# SCH_gauges_v2_2023-05-08.net
KiCad netlist of a schematic drawn in EasyEDA
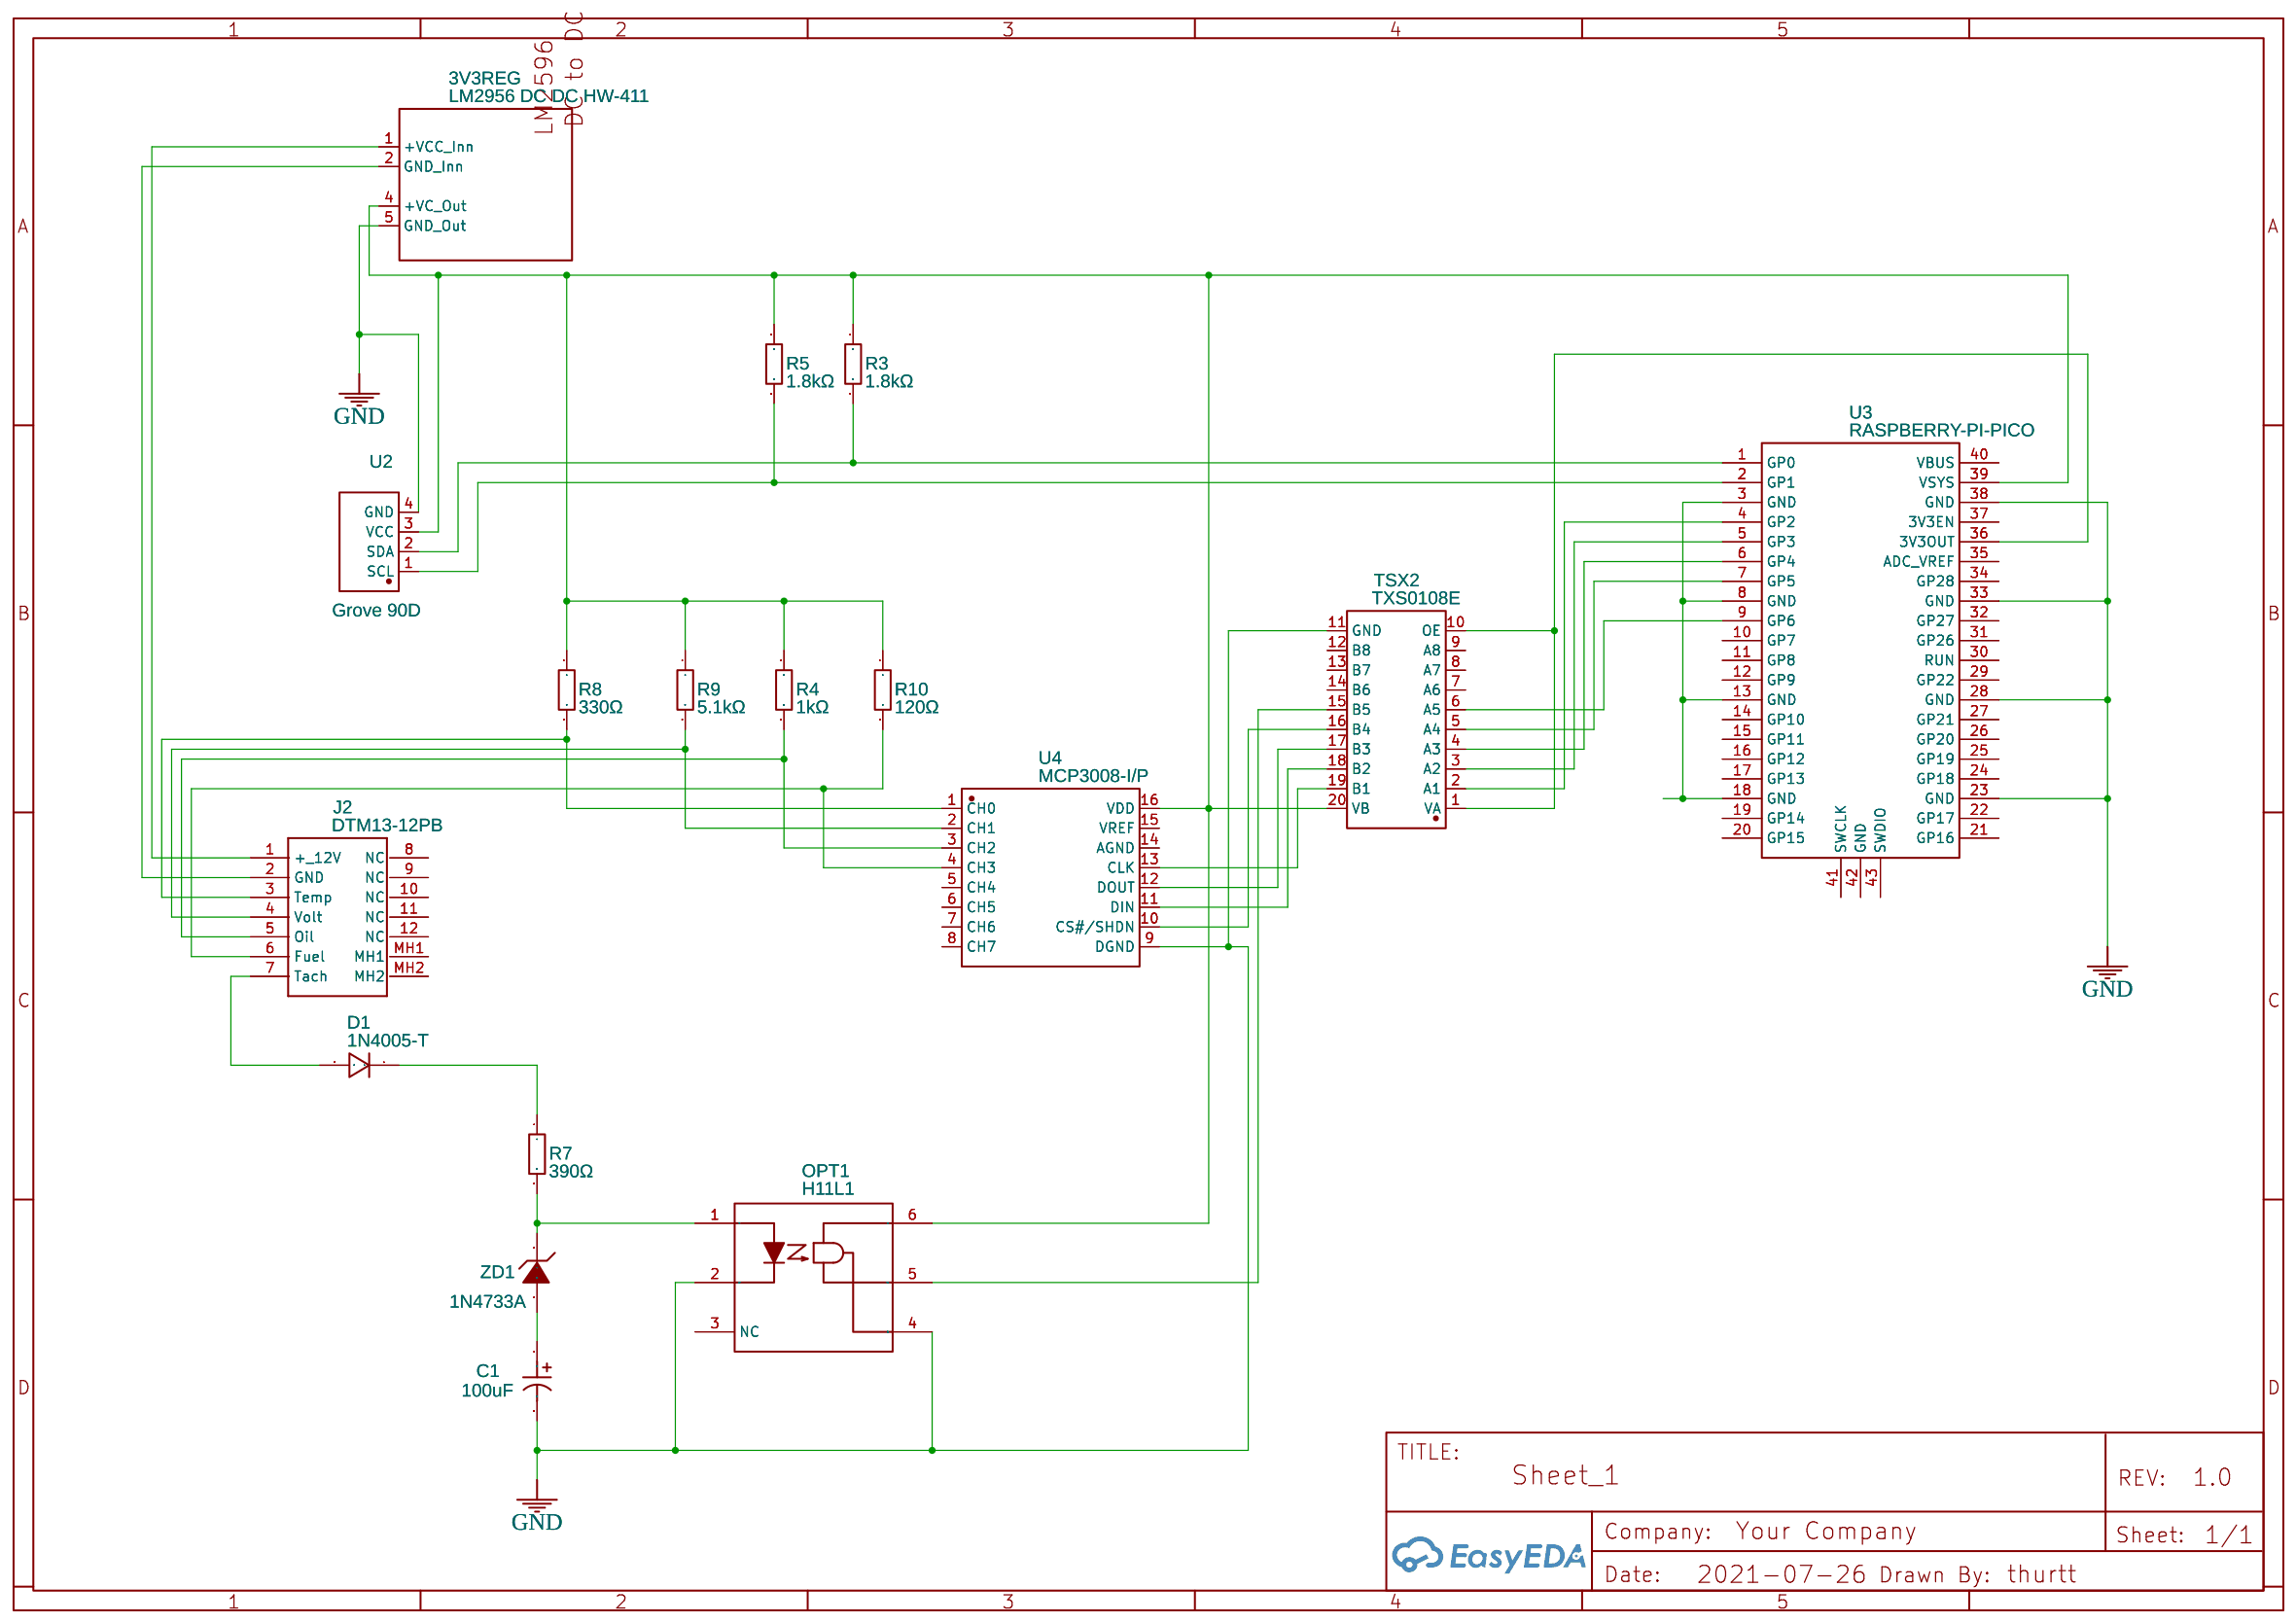
[diagram p0: schematic sheet]

(export (version "E")
  (design (tool "Eeschema 10.0.6"))
  (components
    (comp (ref "3V3REG") (value "LM2956 DC DC HW-411") (libsource (lib "") (part "LM2956 DC DC HW-411")))
    (comp (ref "C1")
      (value "100uF")
      (fields
        (field (name "BOM_Manufacturer Part") "35V100uF CD110")
        (field (name "BOM_Supplier Part") "C2960381")
      )
      (libsource (lib "") (part "35V100UF CD110"))
    )
    (comp (ref "D1")
      (value "1N4005-T")
      (fields (field (name "BOM_Supplier Part") "C211377"))
      (libsource (lib "") (part "1N4005-T"))
    )
    (comp (ref "J2") (value "DTM13-12PB") (libsource (lib "") (part "DTM13-12PB")))
    (comp (ref "OPT1")
      (value "H11L1")
      (fields (field (name "BOM_Supplier Part") "C16587"))
      (libsource (lib "") (part "H11L1"))
    )
    (comp (ref "R3")
      (value "1.8kΩ")
      (fields
        (field (name "BOM_Manufacturer Part") "RN1WS390ΩFT/BA1")
        (field (name "BOM_Supplier Part") "C385382")
      )
      (libsource (lib "") (part "RN1WS390ΩFT/BA1"))
    )
    (comp (ref "R4")
      (value "1kΩ")
      (fields
        (field (name "BOM_Manufacturer Part") "RN1WS390ΩFT/BA1")
        (field (name "BOM_Supplier Part") "C385382")
      )
      (libsource (lib "") (part "RN1WS390ΩFT/BA1"))
    )
    (comp (ref "R5")
      (value "1.8kΩ")
      (fields
        (field (name "BOM_Manufacturer Part") "RN1WS390ΩFT/BA1")
        (field (name "BOM_Supplier Part") "C385382")
      )
      (libsource (lib "") (part "RN1WS390ΩFT/BA1"))
    )
    (comp (ref "R7")
      (value "390Ω")
      (fields
        (field (name "BOM_Manufacturer Part") "RN1WS390ΩFT/BA1")
        (field (name "BOM_Supplier Part") "C385382")
      )
      (libsource (lib "") (part "RN1WS390ΩFT/BA1"))
    )
    (comp (ref "R8")
      (value "330Ω")
      (fields
        (field (name "BOM_Manufacturer Part") "RN1WS390ΩFT/BA1")
        (field (name "BOM_Supplier Part") "C385382")
      )
      (libsource (lib "") (part "RN1WS390ΩFT/BA1"))
    )
    (comp (ref "R9")
      (value "5.1kΩ")
      (fields
        (field (name "BOM_Manufacturer Part") "RN1WS390ΩFT/BA1")
        (field (name "BOM_Supplier Part") "C385382")
      )
      (libsource (lib "") (part "RN1WS390ΩFT/BA1"))
    )
    (comp (ref "R10")
      (value "120Ω")
      (fields
        (field (name "BOM_Manufacturer Part") "RN1WS390ΩFT/BA1")
        (field (name "BOM_Supplier Part") "C385382")
      )
      (libsource (lib "") (part "RN1WS390ΩFT/BA1"))
    )
    (comp (ref "TSX2")
      (value "TXS0108E")
      (fields (field (name "BOM_Supplier Part") "B06XWVZHZJ"))
      (libsource (lib "") (part "TXS0108E DAUGHTERBOARD"))
    )
    (comp (ref "U2") (value "Grove 90D") (libsource (lib "") (part "Grove-2mm-I2C-90D-CONN")))
    (comp (ref "U3") (value "RASPBERRY-PI-PICO") (libsource (lib "") (part "RASPBERRY-PI-PICO")))
    (comp (ref "U4")
      (value "MCP3008-I/P")
      (fields (field (name "BOM_Supplier Part") "C2890491"))
      (libsource (lib "") (part "MCP3008-I/P"))
    )
    (comp (ref "ZD1")
      (value "1N4733A")
      (fields (field (name "BOM_Supplier Part") "C2536"))
      (libsource (lib "") (part "1N4733A_C2536"))
    )
  )
  (nets
    (net (code "1") (name "GND") (class "Default")
      (node (ref "3V3REG") (pin "5") (pinfunction "GND_Out_5") (pintype "unspecified"))
      (node (ref "C1") (pin "2") (pinfunction "2_2") (pintype "input"))
      (node (ref "OPT1") (pin "2") (pinfunction "CAT_2") (pintype "unspecified"))
      (node (ref "OPT1") (pin "4") (pinfunction "VO_4") (pintype "unspecified"))
      (node (ref "TSX2") (pin "11") (pinfunction "GND_11") (pintype "unspecified"))
      (node (ref "U2") (pin "4") (pinfunction "GND_4") (pintype "unspecified"))
      (node (ref "U3") (pin "23") (pinfunction "GND_23") (pintype "unspecified"))
      (node (ref "U3") (pin "28") (pinfunction "GND_28") (pintype "unspecified"))
      (node (ref "U3") (pin "33") (pinfunction "GND_33") (pintype "unspecified"))
      (node (ref "U3") (pin "38") (pinfunction "GND_38") (pintype "unspecified"))
      (node (ref "U4") (pin "9") (pinfunction "DGND_9") (pintype "unspecified"))
    )
    (net (code "2") (name "Net-(3V3REG-+VCC_Inn)") (class "Default")
      (node (ref "3V3REG") (pin "1") (pinfunction "+VCC_Inn_1") (pintype "unspecified"))
      (node (ref "J2") (pin "1") (pinfunction "+_12V_1") (pintype "bidirectional"))
    )
    (net (code "3") (name "Net-(3V3REG-+VC_Out)") (class "Default")
      (node (ref "3V3REG") (pin "4") (pinfunction "+VC_Out_4") (pintype "unspecified"))
      (node (ref "OPT1") (pin "6") (pinfunction "VCC_6") (pintype "unspecified"))
      (node (ref "R10") (pin "1") (pinfunction "1_1") (pintype "unspecified"))
      (node (ref "R3") (pin "1") (pinfunction "1_1") (pintype "unspecified"))
      (node (ref "R4") (pin "1") (pinfunction "1_1") (pintype "unspecified"))
      (node (ref "R5") (pin "1") (pinfunction "1_1") (pintype "unspecified"))
      (node (ref "R8") (pin "1") (pinfunction "1_1") (pintype "unspecified"))
      (node (ref "R9") (pin "1") (pinfunction "1_1") (pintype "unspecified"))
      (node (ref "TSX2") (pin "20") (pinfunction "VB_20") (pintype "unspecified"))
      (node (ref "U2") (pin "3") (pinfunction "VCC_3") (pintype "unspecified"))
      (node (ref "U3") (pin "39") (pinfunction "VSYS_39") (pintype "unspecified"))
      (node (ref "U4") (pin "16") (pinfunction "VDD_16") (pintype "unspecified"))
    )
    (net (code "4") (name "Net-(3V3REG-GND_Inn)") (class "Default")
      (node (ref "3V3REG") (pin "2") (pinfunction "GND_Inn_2") (pintype "unspecified"))
      (node (ref "J2") (pin "2") (pinfunction "GND_2") (pintype "bidirectional"))
    )
    (net (code "5") (name "Net-(D1-Pad1)") (class "Default")
      (node (ref "D1") (pin "1") (pinfunction "1_1") (pintype "unspecified"))
      (node (ref "R7") (pin "1") (pinfunction "1_1") (pintype "unspecified"))
    )
    (net (code "6") (name "Net-(J2-Fuel)") (class "Default")
      (node (ref "J2") (pin "6") (pinfunction "Fuel_6") (pintype "bidirectional"))
      (node (ref "R10") (pin "2") (pinfunction "2_2") (pintype "unspecified"))
      (node (ref "U4") (pin "4") (pinfunction "CH3_4") (pintype "unspecified"))
    )
    (net (code "7") (name "Net-(J2-Oil)") (class "Default")
      (node (ref "J2") (pin "5") (pinfunction "Oil_5") (pintype "bidirectional"))
      (node (ref "R4") (pin "2") (pinfunction "2_2") (pintype "unspecified"))
      (node (ref "U4") (pin "3") (pinfunction "CH2_3") (pintype "unspecified"))
    )
    (net (code "8") (name "Net-(J2-Tach)") (class "Default")
      (node (ref "D1") (pin "2") (pinfunction "2_2") (pintype "unspecified"))
      (node (ref "J2") (pin "7") (pinfunction "Tach_7") (pintype "bidirectional"))
    )
    (net (code "9") (name "Net-(J2-Temp)") (class "Default")
      (node (ref "J2") (pin "3") (pinfunction "Temp_3") (pintype "bidirectional"))
      (node (ref "R8") (pin "2") (pinfunction "2_2") (pintype "unspecified"))
      (node (ref "U4") (pin "1") (pinfunction "CH0_1") (pintype "unspecified"))
    )
    (net (code "10") (name "Net-(J2-Volt)") (class "Default")
      (node (ref "J2") (pin "4") (pinfunction "Volt_4") (pintype "bidirectional"))
      (node (ref "R9") (pin "2") (pinfunction "2_2") (pintype "unspecified"))
      (node (ref "U4") (pin "2") (pinfunction "CH1_2") (pintype "unspecified"))
    )
    (net (code "11") (name "Net-(OPT1-AN)") (class "Default")
      (node (ref "OPT1") (pin "1") (pinfunction "AN_1") (pintype "unspecified"))
      (node (ref "R7") (pin "2") (pinfunction "2_2") (pintype "unspecified"))
      (node (ref "ZD1") (pin "2") (pinfunction "K_2") (pintype "unspecified"))
    )
    (net (code "12") (name "Net-(OPT1-GND)") (class "Default")
      (node (ref "OPT1") (pin "5") (pinfunction "GND_5") (pintype "unspecified"))
      (node (ref "TSX2") (pin "15") (pinfunction "B5_15") (pintype "unspecified"))
    )
    (net (code "13") (name "Net-(TSX2-A1)") (class "Default")
      (node (ref "TSX2") (pin "2") (pinfunction "A1_2") (pintype "unspecified"))
      (node (ref "U3") (pin "4") (pinfunction "GP2_4") (pintype "unspecified"))
    )
    (net (code "14") (name "Net-(TSX2-A2)") (class "Default")
      (node (ref "TSX2") (pin "3") (pinfunction "A2_3") (pintype "unspecified"))
      (node (ref "U3") (pin "5") (pinfunction "GP3_5") (pintype "unspecified"))
    )
    (net (code "15") (name "Net-(TSX2-A3)") (class "Default")
      (node (ref "TSX2") (pin "4") (pinfunction "A3_4") (pintype "unspecified"))
      (node (ref "U3") (pin "6") (pinfunction "GP4_6") (pintype "unspecified"))
    )
    (net (code "16") (name "Net-(TSX2-A4)") (class "Default")
      (node (ref "TSX2") (pin "5") (pinfunction "A4_5") (pintype "unspecified"))
      (node (ref "U3") (pin "7") (pinfunction "GP5_7") (pintype "unspecified"))
    )
    (net (code "17") (name "Net-(TSX2-A5)") (class "Default")
      (node (ref "TSX2") (pin "6") (pinfunction "A5_6") (pintype "unspecified"))
      (node (ref "U3") (pin "9") (pinfunction "GP6_9") (pintype "unspecified"))
    )
    (net (code "18") (name "Net-(TSX2-B1)") (class "Default")
      (node (ref "TSX2") (pin "19") (pinfunction "B1_19") (pintype "unspecified"))
      (node (ref "U4") (pin "13") (pinfunction "CLK_13") (pintype "unspecified"))
    )
    (net (code "19") (name "Net-(TSX2-B2)") (class "Default")
      (node (ref "TSX2") (pin "18") (pinfunction "B2_18") (pintype "unspecified"))
      (node (ref "U4") (pin "11") (pinfunction "DIN_11") (pintype "unspecified"))
    )
    (net (code "20") (name "Net-(TSX2-B3)") (class "Default")
      (node (ref "TSX2") (pin "17") (pinfunction "B3_17") (pintype "unspecified"))
      (node (ref "U4") (pin "12") (pinfunction "DOUT_12") (pintype "unspecified"))
    )
    (net (code "21") (name "Net-(TSX2-B4)") (class "Default")
      (node (ref "TSX2") (pin "16") (pinfunction "B4_16") (pintype "unspecified"))
      (node (ref "U4") (pin "10") (pinfunction "CS#/SHDN_10") (pintype "unspecified"))
    )
    (net (code "22") (name "Net-(TSX2-OE)") (class "Default")
      (node (ref "TSX2") (pin "1") (pinfunction "VA_1") (pintype "unspecified"))
      (node (ref "TSX2") (pin "10") (pinfunction "OE_10") (pintype "unspecified"))
      (node (ref "U3") (pin "36") (pinfunction "3V3OUT_36") (pintype "unspecified"))
    )
    (net (code "23") (name "Net-(U2-SCL)") (class "Default")
      (node (ref "R5") (pin "2") (pinfunction "2_2") (pintype "unspecified"))
      (node (ref "U2") (pin "1") (pinfunction "SCL_1") (pintype "unspecified"))
      (node (ref "U3") (pin "2") (pinfunction "GP1_2") (pintype "unspecified"))
    )
    (net (code "24") (name "Net-(U2-SDA)") (class "Default")
      (node (ref "R3") (pin "2") (pinfunction "2_2") (pintype "unspecified"))
      (node (ref "U2") (pin "2") (pinfunction "SDA_2") (pintype "unspecified"))
      (node (ref "U3") (pin "1") (pinfunction "GP0_1") (pintype "unspecified"))
    )
    (net (code "25") (name "Net-(U3-GND-Pad13)") (class "Default")
      (node (ref "U3") (pin "13") (pinfunction "GND_13") (pintype "unspecified"))
      (node (ref "U3") (pin "18") (pinfunction "GND_18") (pintype "unspecified"))
      (node (ref "U3") (pin "3") (pinfunction "GND_3") (pintype "unspecified"))
      (node (ref "U3") (pin "8") (pinfunction "GND_8") (pintype "unspecified"))
    )
    (net (code "26") (name "Net-(ZD1-A)") (class "Default")
      (node (ref "C1") (pin "1") (pinfunction "1_1") (pintype "input"))
      (node (ref "ZD1") (pin "1") (pinfunction "A_1") (pintype "unspecified"))
    )
    (net (code "27") (name "unconnected-(J2-NC-Pad8)") (class "Default")
      (node (ref "J2") (pin "8") (pinfunction "NC_8") (pintype "bidirectional"))
    )
    (net (code "28") (name "unconnected-(J2-NC-Pad9)") (class "Default")
      (node (ref "J2") (pin "9") (pinfunction "NC_9") (pintype "bidirectional"))
    )
    (net (code "29") (name "unconnected-(J2-NC-Pad10)") (class "Default")
      (node (ref "J2") (pin "10") (pinfunction "NC_10") (pintype "bidirectional"))
    )
    (net (code "30") (name "unconnected-(J2-NC-Pad11)") (class "Default")
      (node (ref "J2") (pin "11") (pinfunction "NC_11") (pintype "bidirectional"))
    )
    (net (code "31") (name "unconnected-(J2-NC-Pad12)") (class "Default")
      (node (ref "J2") (pin "12") (pinfunction "NC_12") (pintype "bidirectional"))
    )
    (net (code "32") (name "unconnected-(J2-PadMH1)") (class "Default")
      (node (ref "J2") (pin "MH1") (pinfunction "MH1_MH1") (pintype "bidirectional"))
    )
    (net (code "33") (name "unconnected-(J2-PadMH2)") (class "Default")
      (node (ref "J2") (pin "MH2") (pinfunction "MH2_MH2") (pintype "bidirectional"))
    )
    (net (code "34") (name "unconnected-(OPT1-NC-Pad3)") (class "Default")
      (node (ref "OPT1") (pin "3") (pinfunction "NC_3") (pintype "unspecified"))
    )
    (net (code "35") (name "unconnected-(TSX2-A6-Pad7)") (class "Default")
      (node (ref "TSX2") (pin "7") (pinfunction "A6_7") (pintype "unspecified"))
    )
    (net (code "36") (name "unconnected-(TSX2-A7-Pad8)") (class "Default")
      (node (ref "TSX2") (pin "8") (pinfunction "A7_8") (pintype "unspecified"))
    )
    (net (code "37") (name "unconnected-(TSX2-A8-Pad9)") (class "Default")
      (node (ref "TSX2") (pin "9") (pinfunction "A8_9") (pintype "unspecified"))
    )
    (net (code "38") (name "unconnected-(TSX2-B6-Pad14)") (class "Default")
      (node (ref "TSX2") (pin "14") (pinfunction "B6_14") (pintype "unspecified"))
    )
    (net (code "39") (name "unconnected-(TSX2-B7-Pad13)") (class "Default")
      (node (ref "TSX2") (pin "13") (pinfunction "B7_13") (pintype "unspecified"))
    )
    (net (code "40") (name "unconnected-(TSX2-B8-Pad12)") (class "Default")
      (node (ref "TSX2") (pin "12") (pinfunction "B8_12") (pintype "unspecified"))
    )
    (net (code "41") (name "unconnected-(U3-3V3EN-Pad37)") (class "Default")
      (node (ref "U3") (pin "37") (pinfunction "3V3EN_37") (pintype "unspecified"))
    )
    (net (code "42") (name "unconnected-(U3-ADC_VREF-Pad35)") (class "Default")
      (node (ref "U3") (pin "35") (pinfunction "ADC_VREF_35") (pintype "unspecified"))
    )
    (net (code "43") (name "unconnected-(U3-GND-Pad42)") (class "Default")
      (node (ref "U3") (pin "42") (pinfunction "GND_42") (pintype "unspecified"))
    )
    (net (code "44") (name "unconnected-(U3-GP7-Pad10)") (class "Default")
      (node (ref "U3") (pin "10") (pinfunction "GP7_10") (pintype "unspecified"))
    )
    (net (code "45") (name "unconnected-(U3-GP8-Pad11)") (class "Default")
      (node (ref "U3") (pin "11") (pinfunction "GP8_11") (pintype "unspecified"))
    )
    (net (code "46") (name "unconnected-(U3-GP9-Pad12)") (class "Default")
      (node (ref "U3") (pin "12") (pinfunction "GP9_12") (pintype "unspecified"))
    )
    (net (code "47") (name "unconnected-(U3-GP10-Pad14)") (class "Default")
      (node (ref "U3") (pin "14") (pinfunction "GP10_14") (pintype "unspecified"))
    )
    (net (code "48") (name "unconnected-(U3-GP11-Pad15)") (class "Default")
      (node (ref "U3") (pin "15") (pinfunction "GP11_15") (pintype "unspecified"))
    )
    (net (code "49") (name "unconnected-(U3-GP12-Pad16)") (class "Default")
      (node (ref "U3") (pin "16") (pinfunction "GP12_16") (pintype "unspecified"))
    )
    (net (code "50") (name "unconnected-(U3-GP13-Pad17)") (class "Default")
      (node (ref "U3") (pin "17") (pinfunction "GP13_17") (pintype "unspecified"))
    )
    (net (code "51") (name "unconnected-(U3-GP14-Pad19)") (class "Default")
      (node (ref "U3") (pin "19") (pinfunction "GP14_19") (pintype "unspecified"))
    )
    (net (code "52") (name "unconnected-(U3-GP15-Pad20)") (class "Default")
      (node (ref "U3") (pin "20") (pinfunction "GP15_20") (pintype "unspecified"))
    )
    (net (code "53") (name "unconnected-(U3-GP16-Pad21)") (class "Default")
      (node (ref "U3") (pin "21") (pinfunction "GP16_21") (pintype "unspecified"))
    )
    (net (code "54") (name "unconnected-(U3-GP17-Pad22)") (class "Default")
      (node (ref "U3") (pin "22") (pinfunction "GP17_22") (pintype "unspecified"))
    )
    (net (code "55") (name "unconnected-(U3-GP18-Pad24)") (class "Default")
      (node (ref "U3") (pin "24") (pinfunction "GP18_24") (pintype "unspecified"))
    )
    (net (code "56") (name "unconnected-(U3-GP19-Pad25)") (class "Default")
      (node (ref "U3") (pin "25") (pinfunction "GP19_25") (pintype "unspecified"))
    )
    (net (code "57") (name "unconnected-(U3-GP20-Pad26)") (class "Default")
      (node (ref "U3") (pin "26") (pinfunction "GP20_26") (pintype "unspecified"))
    )
    (net (code "58") (name "unconnected-(U3-GP21-Pad27)") (class "Default")
      (node (ref "U3") (pin "27") (pinfunction "GP21_27") (pintype "unspecified"))
    )
    (net (code "59") (name "unconnected-(U3-GP22-Pad29)") (class "Default")
      (node (ref "U3") (pin "29") (pinfunction "GP22_29") (pintype "unspecified"))
    )
    (net (code "60") (name "unconnected-(U3-GP26-Pad31)") (class "Default")
      (node (ref "U3") (pin "31") (pinfunction "GP26_31") (pintype "unspecified"))
    )
    (net (code "61") (name "unconnected-(U3-GP27-Pad32)") (class "Default")
      (node (ref "U3") (pin "32") (pinfunction "GP27_32") (pintype "unspecified"))
    )
    (net (code "62") (name "unconnected-(U3-GP28-Pad34)") (class "Default")
      (node (ref "U3") (pin "34") (pinfunction "GP28_34") (pintype "unspecified"))
    )
    (net (code "63") (name "unconnected-(U3-RUN-Pad30)") (class "Default")
      (node (ref "U3") (pin "30") (pinfunction "RUN_30") (pintype "unspecified"))
    )
    (net (code "64") (name "unconnected-(U3-SWCLK-Pad41)") (class "Default")
      (node (ref "U3") (pin "41") (pinfunction "SWCLK_41") (pintype "unspecified"))
    )
    (net (code "65") (name "unconnected-(U3-SWDIO-Pad43)") (class "Default")
      (node (ref "U3") (pin "43") (pinfunction "SWDIO_43") (pintype "unspecified"))
    )
    (net (code "66") (name "unconnected-(U3-VBUS-Pad40)") (class "Default")
      (node (ref "U3") (pin "40") (pinfunction "VBUS_40") (pintype "unspecified"))
    )
    (net (code "67") (name "unconnected-(U4-AGND-Pad14)") (class "Default")
      (node (ref "U4") (pin "14") (pinfunction "AGND_14") (pintype "unspecified"))
    )
    (net (code "68") (name "unconnected-(U4-CH4-Pad5)") (class "Default")
      (node (ref "U4") (pin "5") (pinfunction "CH4_5") (pintype "unspecified"))
    )
    (net (code "69") (name "unconnected-(U4-CH5-Pad6)") (class "Default")
      (node (ref "U4") (pin "6") (pinfunction "CH5_6") (pintype "unspecified"))
    )
    (net (code "70") (name "unconnected-(U4-CH6-Pad7)") (class "Default")
      (node (ref "U4") (pin "7") (pinfunction "CH6_7") (pintype "unspecified"))
    )
    (net (code "71") (name "unconnected-(U4-CH7-Pad8)") (class "Default")
      (node (ref "U4") (pin "8") (pinfunction "CH7_8") (pintype "unspecified"))
    )
    (net (code "72") (name "unconnected-(U4-VREF-Pad15)") (class "Default")
      (node (ref "U4") (pin "15") (pinfunction "VREF_15") (pintype "unspecified"))
    )
  )
)
